# Startup_Delay.net
KiCad netlist of a schematic drawn in Altium Designer
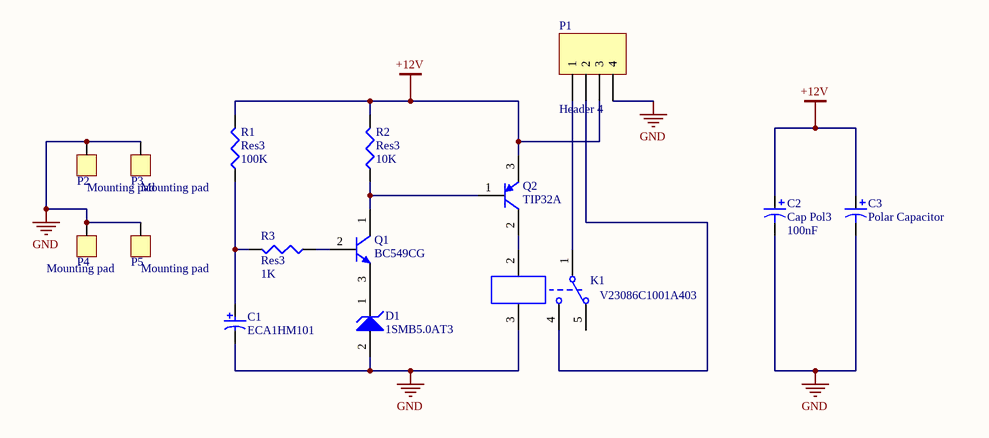
[diagram p0: Startup Delay.SchDoc]

(export (version "E")
  (design (tool "Eeschema 10.0.6"))
  (components
    (comp (ref "C1")
      (value "ECA1HM101")
      (footprint "CAPPR65-350-1150X800X1250")
      (description "Aluminum Electrolytic Capacitor, 100 uF, +/- 20%, 50 V, -40 to 85 degC, 2-Pin THD, RoHS, Bulk")
      (fields (field (name "MANUFACTURER") "Panasonic") (field (name "VOLTAGE") "50V"))
      (libsource (lib "Altium Content Vault") (part "CAP-P-2"))
    )
    (comp (ref "C2")
      (value "Cap Pol3")
      (footprint "C0805")
      (description "Polarized Capacitor (Surface Mount)")
      (fields (field (name "ALTIUM_VALUE") "100nF") (field (name "PUBLISHER") "Altium Limited"))
      (libsource (lib "Miscellaneous Devices") (part "Cap Pol3"))
    )
    (comp (ref "C3")
      (value "Polar Capacitor")
      (footprint "Case D")
      (libsource (lib "CurrentSource") (part "Polar Capacitor"))
    )
    (comp (ref "D1")
      (value "1SMB5.0AT3")
      (footprint "ONSC-SMB-2-403A-03_H_V")
      (description "600 W Peak Power Zener Transient Voltage Suppressor, Unidirectional, 2-Pin SMB, Tape and Reel")
      (fields (field (name "MANUFACTURER") "On Semiconductor"))
      (libsource (lib "Altium Content Vault") (part "ONSC-K1A2-2"))
    )
    (comp (ref "K1")
      (value "V23086C1001A403")
      (footprint "RELAY_SPDT_5")
      (description "TE Connectivity SPDT PCB Mount Automotive Relay, 12V DC Coil, -40 to 105 degC, 5-Pin THD, RoHS")
      (fields (field (name "MANUFACTURER") "TE Connectivity"))
      (libsource (lib "Altium Content Vault") (part "RELAY-SPDT-5_M"))
    )
    (comp (ref "P1")
      (value "Header 4")
      (footprint "HDR1X4")
      (description "Header, 4-Pin")
      (fields (field (name "PUBLISHER") "Altium Limited"))
      (libsource (lib "Miscellaneous Connectors") (part "Header 4"))
    )
    (comp (ref "P2")
      (value "Mounting pad")
      (footprint "Mounting pad")
      (libsource (lib "CurrentSource") (part "Mounting pad"))
    )
    (comp (ref "P3")
      (value "Mounting pad")
      (footprint "Mounting pad")
      (libsource (lib "CurrentSource") (part "Mounting pad"))
    )
    (comp (ref "P4")
      (value "Mounting pad")
      (footprint "Mounting pad")
      (libsource (lib "CurrentSource") (part "Mounting pad"))
    )
    (comp (ref "P5")
      (value "Mounting pad")
      (footprint "Mounting pad")
      (libsource (lib "CurrentSource") (part "Mounting pad"))
    )
    (comp (ref "Q1")
      (value "BC549CG")
      (footprint "ONSC-TO-92-3-29-04_AD")
      (description "Low Noise Transistor, NPN Silicon, 3-Pin TO-92, Pb-Free, Bulk Box")
      (fields (field (name "MANUFACTURER") "On Semiconductor"))
      (libsource (lib "Altium Content Vault") (part "ONSC-NPN-C1B2E3-3"))
    )
    (comp (ref "Q2")
      (value "TIP32A")
      (footprint "ONSC-TO-220-3-221A-09")
      (description "Complementary Silicon Plastic Power Transistor, 3-Pin TO-220, Tube")
      (fields (field (name "MANUFACTURER") "On Semiconductor"))
      (libsource (lib "Altium Content Vault") (part "CMP-1048-01079-1"))
    )
    (comp (ref "R1")
      (value "Res3")
      (footprint "J1-0603")
      (description "Resistor")
      (fields (field (name "ALTIUM_VALUE") "100K") (field (name "PUBLISHER") "Altium Limited"))
      (libsource (lib "Miscellaneous Devices") (part "Res3"))
    )
    (comp (ref "R2")
      (value "Res3")
      (footprint "J1-0603")
      (description "Resistor")
      (fields (field (name "ALTIUM_VALUE") "10K") (field (name "PUBLISHER") "Altium Limited"))
      (libsource (lib "Miscellaneous Devices") (part "Res3"))
    )
    (comp (ref "R3")
      (value "Res3")
      (footprint "J1-0603")
      (description "Resistor")
      (fields (field (name "ALTIUM_VALUE") "1K") (field (name "PUBLISHER") "Altium Limited"))
      (libsource (lib "Miscellaneous Devices") (part "Res3"))
    )
  )
  (nets
    (net (code "1") (name "+12V") (class "Default")
      (node (ref "C2") (pin "1") (pinfunction "1_1") (pintype "passive"))
      (node (ref "C3") (pin "1") (pinfunction "1_1") (pintype "passive"))
      (node (ref "P1") (pin "3") (pinfunction "3_3") (pintype "passive"))
      (node (ref "Q2") (pin "3") (pinfunction "E_3") (pintype "passive"))
      (node (ref "R1") (pin "2") (pinfunction "2_2") (pintype "passive"))
      (node (ref "R2") (pin "2") (pinfunction "2_2") (pintype "passive"))
    )
    (net (code "2") (name "GND") (class "Default")
      (node (ref "C1") (pin "2") (pinfunction "2_2") (pintype "passive"))
      (node (ref "C2") (pin "2") (pinfunction "2_2") (pintype "passive"))
      (node (ref "C3") (pin "2") (pinfunction "2_2") (pintype "passive"))
      (node (ref "D1") (pin "2") (pinfunction "A_2") (pintype "passive"))
      (node (ref "K1") (pin "3") (pinfunction "3_3") (pintype "passive"))
      (node (ref "P1") (pin "4") (pinfunction "4_4") (pintype "passive"))
      (node (ref "P2") (pin "1") (pinfunction "1_1") (pintype "passive"))
      (node (ref "P3") (pin "1") (pinfunction "1_1") (pintype "passive"))
      (node (ref "P4") (pin "1") (pinfunction "1_1") (pintype "passive"))
      (node (ref "P5") (pin "1") (pinfunction "1_1") (pintype "passive"))
    )
    (net (code "3") (name "Net-(C1-Pad1)") (class "Default")
      (node (ref "C1") (pin "1") (pinfunction "1_1") (pintype "passive"))
      (node (ref "R1") (pin "1") (pinfunction "1_1") (pintype "passive"))
      (node (ref "R3") (pin "2") (pinfunction "2_2") (pintype "passive"))
    )
    (net (code "4") (name "Net-(D1-K)") (class "Default")
      (node (ref "D1") (pin "1") (pinfunction "K_1") (pintype "passive"))
      (node (ref "Q1") (pin "3") (pinfunction "E_3") (pintype "passive"))
    )
    (net (code "5") (name "Net-(K1-Pad1)") (class "Default")
      (node (ref "K1") (pin "1") (pinfunction "1_1") (pintype "passive"))
      (node (ref "P1") (pin "1") (pinfunction "1_1") (pintype "passive"))
    )
    (net (code "6") (name "Net-(K1-Pad4)") (class "Default")
      (node (ref "K1") (pin "4") (pinfunction "4_4") (pintype "passive"))
      (node (ref "P1") (pin "2") (pinfunction "2_2") (pintype "passive"))
    )
    (net (code "7") (name "Net-(Q1-B)") (class "Default")
      (node (ref "Q1") (pin "2") (pinfunction "B_2") (pintype "passive"))
      (node (ref "R3") (pin "1") (pinfunction "1_1") (pintype "passive"))
    )
    (net (code "8") (name "Net-(Q1-C)") (class "Default")
      (node (ref "Q1") (pin "1") (pinfunction "C_1") (pintype "passive"))
      (node (ref "Q2") (pin "1") (pinfunction "B_1") (pintype "passive"))
      (node (ref "R2") (pin "1") (pinfunction "1_1") (pintype "passive"))
    )
    (net (code "9") (name "Net-(Q2-C)") (class "Default")
      (node (ref "K1") (pin "2") (pinfunction "2_2") (pintype "passive"))
      (node (ref "Q2") (pin "2") (pinfunction "C_2") (pintype "passive"))
    )
    (net (code "10") (name "unconnected-(K1-Pad5)") (class "Default")
      (node (ref "K1") (pin "5") (pinfunction "5_5") (pintype "passive"))
    )
  )
)
